# power-management-ctt.net
KiCad netlist of a schematic drawn in Altium Designer
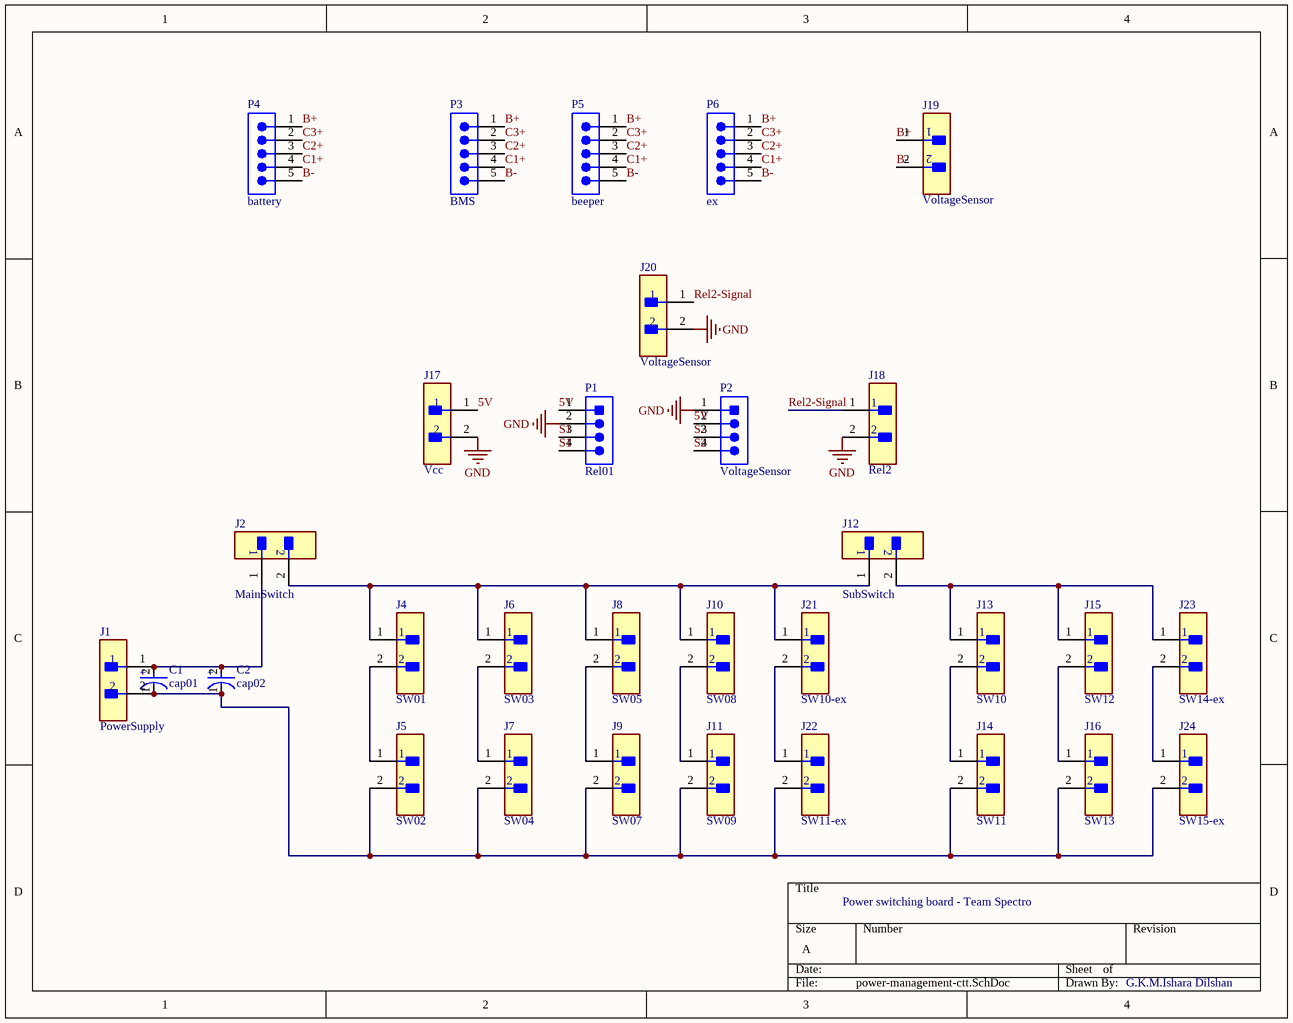
[diagram p0: power-management-ctt.SchDoc]

(export (version "E")
  (design (tool "Eeschema 10.0.6"))
  (components
    (comp (ref "C1")
      (value "cap01")
      (footprint "FP-RAD-TH-D_16_0_5-L_25_2-MFG")
      (description "Aluminum Electrolytic Capacitors (Radial Lead Type) 4700uF ±20% 16V")
      (fields (field (name "TOLERANCE") "20%") (field (name "VOLTAGE") "16V"))
      (libsource (lib "Altium Content Vault") (part "203bc49f2ac43e59fd269a8c329ed05"))
    )
    (comp (ref "C2")
      (value "cap02")
      (footprint "FP-RAD-TH-D_16_0_5-L_25_2-MFG")
      (description "Aluminum Electrolytic Capacitors (Radial Lead Type) 4700uF ±20% 16V")
      (fields (field (name "TOLERANCE") "20%") (field (name "VOLTAGE") "16V"))
      (libsource (lib "Altium Content Vault") (part "203bc49f2ac43e59fd269a8c329ed05"))
    )
    (comp (ref "J1")
      (value "PowerSupply")
      (footprint "FP-M20-9990245-MFG")
      (description "CONN HEADER VERT 2POS 2.54MM")
      (fields (field (name "VOLTAGE") "50V"))
      (libsource (lib "") (part "3bc925449376181038e59eaffc5286c_1"))
    )
    (comp (ref "J2")
      (value "MainSwitch")
      (footprint "FP-M20-9990245-MFG")
      (description "CONN HEADER VERT 2POS 2.54MM")
      (fields (field (name "VOLTAGE") "50V"))
      (libsource (lib "") (part "3bc925449376181038e59eaffc5286c_2"))
    )
    (comp (ref "J4")
      (value "SW01")
      (footprint "FP-M20-9990245-MFG")
      (description "CONN HEADER VERT 2POS 2.54MM")
      (fields (field (name "VOLTAGE") "50V"))
      (libsource (lib "Altium Content Vault") (part "3bc925449376181038e59eaffc5286c"))
    )
    (comp (ref "J5")
      (value "SW02")
      (footprint "FP-M20-9990245-MFG")
      (description "CONN HEADER VERT 2POS 2.54MM")
      (fields (field (name "VOLTAGE") "50V"))
      (libsource (lib "Altium Content Vault") (part "3bc925449376181038e59eaffc5286c"))
    )
    (comp (ref "J6")
      (value "SW03")
      (footprint "FP-M20-9990245-MFG")
      (description "CONN HEADER VERT 2POS 2.54MM")
      (fields (field (name "VOLTAGE") "50V"))
      (libsource (lib "Altium Content Vault") (part "3bc925449376181038e59eaffc5286c"))
    )
    (comp (ref "J7")
      (value "SW04")
      (footprint "FP-M20-9990245-MFG")
      (description "CONN HEADER VERT 2POS 2.54MM")
      (fields (field (name "VOLTAGE") "50V"))
      (libsource (lib "Altium Content Vault") (part "3bc925449376181038e59eaffc5286c"))
    )
    (comp (ref "J8")
      (value "SW05")
      (footprint "FP-M20-9990245-MFG")
      (description "CONN HEADER VERT 2POS 2.54MM")
      (fields (field (name "VOLTAGE") "50V"))
      (libsource (lib "Altium Content Vault") (part "3bc925449376181038e59eaffc5286c"))
    )
    (comp (ref "J9")
      (value "SW07")
      (footprint "FP-M20-9990245-MFG")
      (description "CONN HEADER VERT 2POS 2.54MM")
      (fields (field (name "VOLTAGE") "50V"))
      (libsource (lib "Altium Content Vault") (part "3bc925449376181038e59eaffc5286c"))
    )
    (comp (ref "J10")
      (value "SW08")
      (footprint "FP-M20-9990245-MFG")
      (description "CONN HEADER VERT 2POS 2.54MM")
      (fields (field (name "VOLTAGE") "50V"))
      (libsource (lib "Altium Content Vault") (part "3bc925449376181038e59eaffc5286c"))
    )
    (comp (ref "J11")
      (value "SW09")
      (footprint "FP-M20-9990245-MFG")
      (description "CONN HEADER VERT 2POS 2.54MM")
      (fields (field (name "VOLTAGE") "50V"))
      (libsource (lib "Altium Content Vault") (part "3bc925449376181038e59eaffc5286c"))
    )
    (comp (ref "J12")
      (value "SubSwitch")
      (footprint "FP-M20-9990245-MFG")
      (description "CONN HEADER VERT 2POS 2.54MM")
      (fields (field (name "VOLTAGE") "50V"))
      (libsource (lib "") (part "3bc925449376181038e59eaffc5286c_2"))
    )
    (comp (ref "J13")
      (value "SW10")
      (footprint "FP-M20-9990245-MFG")
      (description "CONN HEADER VERT 2POS 2.54MM")
      (fields (field (name "VOLTAGE") "50V"))
      (libsource (lib "Altium Content Vault") (part "3bc925449376181038e59eaffc5286c"))
    )
    (comp (ref "J14")
      (value "SW11")
      (footprint "FP-M20-9990245-MFG")
      (description "CONN HEADER VERT 2POS 2.54MM")
      (fields (field (name "VOLTAGE") "50V"))
      (libsource (lib "Altium Content Vault") (part "3bc925449376181038e59eaffc5286c"))
    )
    (comp (ref "J15")
      (value "SW12")
      (footprint "FP-M20-9990245-MFG")
      (description "CONN HEADER VERT 2POS 2.54MM")
      (fields (field (name "VOLTAGE") "50V"))
      (libsource (lib "Altium Content Vault") (part "3bc925449376181038e59eaffc5286c"))
    )
    (comp (ref "J16")
      (value "SW13")
      (footprint "FP-M20-9990245-MFG")
      (description "CONN HEADER VERT 2POS 2.54MM")
      (fields (field (name "VOLTAGE") "50V"))
      (libsource (lib "Altium Content Vault") (part "3bc925449376181038e59eaffc5286c"))
    )
    (comp (ref "J17")
      (value "Vcc")
      (footprint "FP-M20-9990245-MFG")
      (description "CONN HEADER VERT 2POS 2.54MM")
      (fields (field (name "VOLTAGE") "50V"))
      (libsource (lib "") (part "3bc925449376181038e59eaffc5286c_1"))
    )
    (comp (ref "J18")
      (value "Rel2")
      (footprint "FP-M20-9990245-MFG")
      (description "CONN HEADER VERT 2POS 2.54MM")
      (fields (field (name "VOLTAGE") "50V"))
      (libsource (lib "Altium Content Vault") (part "3bc925449376181038e59eaffc5286c"))
    )
    (comp (ref "J19")
      (value "VoltageSensor")
      (footprint "FP-M20-9990245-MFG")
      (description "CONN HEADER VERT 2POS 2.54MM")
      (fields (field (name "VOLTAGE") "50V"))
      (libsource (lib "Altium Content Vault") (part "3bc925449376181038e59eaffc5286c"))
    )
    (comp (ref "J20")
      (value "VoltageSensor")
      (footprint "FP-M20-9990245-MFG")
      (description "CONN HEADER VERT 2POS 2.54MM")
      (fields (field (name "VOLTAGE") "50V"))
      (libsource (lib "") (part "3bc925449376181038e59eaffc5286c_1"))
    )
    (comp (ref "J21")
      (value "SW10-ex")
      (footprint "FP-M20-9990245-MFG")
      (description "CONN HEADER VERT 2POS 2.54MM")
      (fields (field (name "VOLTAGE") "50V"))
      (libsource (lib "Altium Content Vault") (part "3bc925449376181038e59eaffc5286c"))
    )
    (comp (ref "J22")
      (value "SW11-ex")
      (footprint "FP-M20-9990245-MFG")
      (description "CONN HEADER VERT 2POS 2.54MM")
      (fields (field (name "VOLTAGE") "50V"))
      (libsource (lib "Altium Content Vault") (part "3bc925449376181038e59eaffc5286c"))
    )
    (comp (ref "J23")
      (value "SW14-ex")
      (footprint "FP-M20-9990245-MFG")
      (description "CONN HEADER VERT 2POS 2.54MM")
      (fields (field (name "VOLTAGE") "50V"))
      (libsource (lib "Altium Content Vault") (part "3bc925449376181038e59eaffc5286c"))
    )
    (comp (ref "J24")
      (value "SW15-ex")
      (footprint "FP-M20-9990245-MFG")
      (description "CONN HEADER VERT 2POS 2.54MM")
      (fields (field (name "VOLTAGE") "50V"))
      (libsource (lib "Altium Content Vault") (part "3bc925449376181038e59eaffc5286c"))
    )
    (comp (ref "P1")
      (value "Rel01")
      (footprint "MOLX-22-27-2041_V")
      (description "Male Header, Pitch 2.54 mm, 1 x 4 Position, Height 11.7 mm, Tail Length 3.56 mm, RoHS, Bulk")
      (fields (field (name "MANUFACTURER") "Molex"))
      (libsource (lib "Altium Content Vault") (part "CN-1P-M-R4"))
    )
    (comp (ref "P2")
      (value "VoltageSensor")
      (footprint "MOLX-22-27-2041_V")
      (description "Male Header, Pitch 2.54 mm, 1 x 4 Position, Height 11.7 mm, Tail Length 3.56 mm, RoHS, Bulk")
      (fields (field (name "MANUFACTURER") "Molex"))
      (libsource (lib "Altium Content Vault") (part "CN-1P-M-R4"))
    )
    (comp (ref "P3")
      (value "BMS")
      (footprint "691311500105")
      (fields (field (name "VOLTAGE") "300V"))
      (libsource (lib "Altium Content Vault") (part "TBL - 1R - 05P - Male"))
    )
    (comp (ref "P4")
      (value "battery")
      (footprint "691311500105")
      (fields (field (name "VOLTAGE") "300V"))
      (libsource (lib "Altium Content Vault") (part "TBL - 1R - 05P - Male"))
    )
    (comp (ref "P5")
      (value "beeper")
      (footprint "691311500105")
      (fields (field (name "VOLTAGE") "300V"))
      (libsource (lib "Altium Content Vault") (part "TBL - 1R - 05P - Male"))
    )
    (comp (ref "P6")
      (value "ex")
      (footprint "691311500105")
      (fields (field (name "VOLTAGE") "300V"))
      (libsource (lib "Altium Content Vault") (part "TBL - 1R - 05P - Male"))
    )
  )
  (nets
    (net (code "1") (name "/5V") (class "Default")
      (node (ref "J17") (pin "1") (pinfunction "1_1") (pintype "passive"))
      (node (ref "P1") (pin "1") (pinfunction "1_1") (pintype "passive"))
      (node (ref "P2") (pin "2") (pinfunction "2_2") (pintype "passive"))
    )
    (net (code "2") (name "/B+") (class "Default")
      (node (ref "J19") (pin "1") (pinfunction "1_1") (pintype "passive"))
      (node (ref "P3") (pin "1") (pinfunction "1_1") (pintype "passive"))
      (node (ref "P4") (pin "1") (pinfunction "1_1") (pintype "passive"))
      (node (ref "P5") (pin "1") (pinfunction "1_1") (pintype "passive"))
      (node (ref "P6") (pin "1") (pinfunction "1_1") (pintype "passive"))
    )
    (net (code "3") (name "/B-") (class "Default")
      (node (ref "J19") (pin "2") (pinfunction "2_2") (pintype "passive"))
      (node (ref "P3") (pin "5") (pinfunction "5_5") (pintype "passive"))
      (node (ref "P4") (pin "5") (pinfunction "5_5") (pintype "passive"))
      (node (ref "P5") (pin "5") (pinfunction "5_5") (pintype "passive"))
      (node (ref "P6") (pin "5") (pinfunction "5_5") (pintype "passive"))
    )
    (net (code "4") (name "/C1+") (class "Default")
      (node (ref "P3") (pin "4") (pinfunction "4_4") (pintype "passive"))
      (node (ref "P4") (pin "4") (pinfunction "4_4") (pintype "passive"))
      (node (ref "P5") (pin "4") (pinfunction "4_4") (pintype "passive"))
      (node (ref "P6") (pin "4") (pinfunction "4_4") (pintype "passive"))
    )
    (net (code "5") (name "/C2+") (class "Default")
      (node (ref "P3") (pin "3") (pinfunction "3_3") (pintype "passive"))
      (node (ref "P4") (pin "3") (pinfunction "3_3") (pintype "passive"))
      (node (ref "P5") (pin "3") (pinfunction "3_3") (pintype "passive"))
      (node (ref "P6") (pin "3") (pinfunction "3_3") (pintype "passive"))
    )
    (net (code "6") (name "/C3+") (class "Default")
      (node (ref "P3") (pin "2") (pinfunction "2_2") (pintype "passive"))
      (node (ref "P4") (pin "2") (pinfunction "2_2") (pintype "passive"))
      (node (ref "P5") (pin "2") (pinfunction "2_2") (pintype "passive"))
      (node (ref "P6") (pin "2") (pinfunction "2_2") (pintype "passive"))
    )
    (net (code "7") (name "/Rel2-Signal") (class "Default")
      (node (ref "J18") (pin "1") (pinfunction "1_1") (pintype "passive"))
      (node (ref "J20") (pin "1") (pinfunction "1_1") (pintype "passive"))
    )
    (net (code "8") (name "/S1") (class "Default")
      (node (ref "P1") (pin "3") (pinfunction "3_3") (pintype "passive"))
      (node (ref "P1") (pin "4") (pinfunction "4_4") (pintype "passive"))
    )
    (net (code "9") (name "/S2") (class "Default")
      (node (ref "P2") (pin "3") (pinfunction "3_3") (pintype "passive"))
      (node (ref "P2") (pin "4") (pinfunction "4_4") (pintype "passive"))
    )
    (net (code "10") (name "GND") (class "Default")
      (node (ref "J17") (pin "2") (pinfunction "2_2") (pintype "passive"))
      (node (ref "J18") (pin "2") (pinfunction "2_2") (pintype "passive"))
      (node (ref "J20") (pin "2") (pinfunction "2_2") (pintype "passive"))
      (node (ref "P1") (pin "2") (pinfunction "2_2") (pintype "passive"))
      (node (ref "P2") (pin "1") (pinfunction "1_1") (pintype "passive"))
    )
    (net (code "11") (name "Net-(C1-A)") (class "Default")
      (node (ref "C1") (pin "2") (pinfunction "A_2") (pintype "passive"))
      (node (ref "C2") (pin "2") (pinfunction "A_2") (pintype "passive"))
      (node (ref "J1") (pin "1") (pinfunction "1_1") (pintype "passive"))
      (node (ref "J2") (pin "1") (pinfunction "1_1") (pintype "passive"))
    )
    (net (code "12") (name "Net-(C1-C)") (class "Default")
      (node (ref "C1") (pin "1") (pinfunction "C_1") (pintype "passive"))
      (node (ref "C2") (pin "1") (pinfunction "C_1") (pintype "passive"))
      (node (ref "J1") (pin "2") (pinfunction "2_2") (pintype "passive"))
      (node (ref "J11") (pin "2") (pinfunction "2_2") (pintype "passive"))
      (node (ref "J14") (pin "2") (pinfunction "2_2") (pintype "passive"))
      (node (ref "J16") (pin "2") (pinfunction "2_2") (pintype "passive"))
      (node (ref "J22") (pin "2") (pinfunction "2_2") (pintype "passive"))
      (node (ref "J24") (pin "2") (pinfunction "2_2") (pintype "passive"))
      (node (ref "J5") (pin "2") (pinfunction "2_2") (pintype "passive"))
      (node (ref "J7") (pin "2") (pinfunction "2_2") (pintype "passive"))
      (node (ref "J9") (pin "2") (pinfunction "2_2") (pintype "passive"))
    )
    (net (code "13") (name "Net-(J4-Pad2)") (class "Default")
      (node (ref "J4") (pin "2") (pinfunction "2_2") (pintype "passive"))
      (node (ref "J5") (pin "1") (pinfunction "1_1") (pintype "passive"))
    )
    (net (code "14") (name "Net-(J6-Pad2)") (class "Default")
      (node (ref "J6") (pin "2") (pinfunction "2_2") (pintype "passive"))
      (node (ref "J7") (pin "1") (pinfunction "1_1") (pintype "passive"))
    )
    (net (code "15") (name "Net-(J8-Pad2)") (class "Default")
      (node (ref "J8") (pin "2") (pinfunction "2_2") (pintype "passive"))
      (node (ref "J9") (pin "1") (pinfunction "1_1") (pintype "passive"))
    )
    (net (code "16") (name "Net-(J10-Pad1)") (class "Default")
      (node (ref "J10") (pin "1") (pinfunction "1_1") (pintype "passive"))
      (node (ref "J12") (pin "1") (pinfunction "1_1") (pintype "passive"))
      (node (ref "J2") (pin "2") (pinfunction "2_2") (pintype "passive"))
      (node (ref "J21") (pin "1") (pinfunction "1_1") (pintype "passive"))
      (node (ref "J4") (pin "1") (pinfunction "1_1") (pintype "passive"))
      (node (ref "J6") (pin "1") (pinfunction "1_1") (pintype "passive"))
      (node (ref "J8") (pin "1") (pinfunction "1_1") (pintype "passive"))
    )
    (net (code "17") (name "Net-(J10-Pad2)") (class "Default")
      (node (ref "J10") (pin "2") (pinfunction "2_2") (pintype "passive"))
      (node (ref "J11") (pin "1") (pinfunction "1_1") (pintype "passive"))
    )
    (net (code "18") (name "Net-(J12-Pad2)") (class "Default")
      (node (ref "J12") (pin "2") (pinfunction "2_2") (pintype "passive"))
      (node (ref "J13") (pin "1") (pinfunction "1_1") (pintype "passive"))
      (node (ref "J15") (pin "1") (pinfunction "1_1") (pintype "passive"))
      (node (ref "J23") (pin "1") (pinfunction "1_1") (pintype "passive"))
    )
    (net (code "19") (name "Net-(J13-Pad2)") (class "Default")
      (node (ref "J13") (pin "2") (pinfunction "2_2") (pintype "passive"))
      (node (ref "J14") (pin "1") (pinfunction "1_1") (pintype "passive"))
    )
    (net (code "20") (name "Net-(J15-Pad2)") (class "Default")
      (node (ref "J15") (pin "2") (pinfunction "2_2") (pintype "passive"))
      (node (ref "J16") (pin "1") (pinfunction "1_1") (pintype "passive"))
    )
    (net (code "21") (name "Net-(J21-Pad2)") (class "Default")
      (node (ref "J21") (pin "2") (pinfunction "2_2") (pintype "passive"))
      (node (ref "J22") (pin "1") (pinfunction "1_1") (pintype "passive"))
    )
    (net (code "22") (name "Net-(J23-Pad2)") (class "Default")
      (node (ref "J23") (pin "2") (pinfunction "2_2") (pintype "passive"))
      (node (ref "J24") (pin "1") (pinfunction "1_1") (pintype "passive"))
    )
  )
)
